# PSOC_10pin_to_ZIF.net
KiCad netlist of a schematic drawn in EAGLE
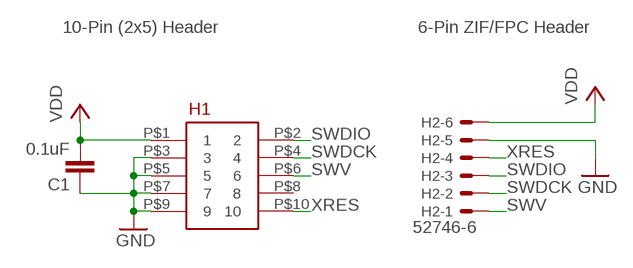
[diagram p0: schematic, sheet 1]

(export (version "E")
  (design (tool "Eeschema 10.0.6"))
  (components
    (comp (ref "C1")
      (value "0.1uF")
      (footprint "eagle-import:CAPC1608X90N")
      (libsource (lib "eagle-import") (part "CC0603-N"))
    )
    (comp (ref "H1")
      (value "2X5_SMD_HEADER_1.27MM")
      (footprint "eagle-import:2X5_SMD_HEADER_1.27MM")
      (libsource (lib "eagle-import") (part "2X5_SMD_HEADER_1.27MM"))
    )
    (comp (ref "H2")
      (value "52746-6")
      (footprint "eagle-import:52746-6")
      (libsource (lib "eagle-import") (part "52746-6"))
    )
  )
  (nets
    (net (code "1") (name "/SWDCK") (class "Default")
      (node (ref "H1") (pin "P$4") (pinfunction "4_P$4") (pintype "bidirectional"))
      (node (ref "H2") (pin "2") (pinfunction "S_2") (pintype "passive"))
    )
    (net (code "2") (name "/SWDIO") (class "Default")
      (node (ref "H1") (pin "P$2") (pinfunction "2_P$2") (pintype "bidirectional"))
      (node (ref "H2") (pin "3") (pinfunction "S_3") (pintype "passive"))
    )
    (net (code "3") (name "/SWV") (class "Default")
      (node (ref "H1") (pin "P$6") (pinfunction "6_P$6") (pintype "bidirectional"))
      (node (ref "H2") (pin "1") (pinfunction "S_1") (pintype "passive"))
    )
    (net (code "4") (name "/XRES") (class "Default")
      (node (ref "H1") (pin "P$10") (pinfunction "10_P$10") (pintype "bidirectional"))
      (node (ref "H2") (pin "4") (pinfunction "S_4") (pintype "passive"))
    )
    (net (code "5") (name "GND") (class "Default")
      (node (ref "C1") (pin "1") (pinfunction "1_1") (pintype "passive"))
      (node (ref "H1") (pin "P$3") (pinfunction "3_P$3") (pintype "bidirectional"))
      (node (ref "H1") (pin "P$5") (pinfunction "5_P$5") (pintype "bidirectional"))
      (node (ref "H1") (pin "P$7") (pinfunction "7_P$7") (pintype "bidirectional"))
      (node (ref "H1") (pin "P$9") (pinfunction "9_P$9") (pintype "bidirectional"))
      (node (ref "H2") (pin "5") (pinfunction "S_5") (pintype "passive"))
    )
    (net (code "6") (name "VDD") (class "Default")
      (node (ref "C1") (pin "2") (pinfunction "2_2") (pintype "passive"))
      (node (ref "H1") (pin "P$1") (pinfunction "1_P$1") (pintype "bidirectional"))
      (node (ref "H2") (pin "6") (pinfunction "S_6") (pintype "passive"))
    )
    (net (code "7") (name "unconnected-(H1-8-PadP$8)") (class "Default")
      (node (ref "H1") (pin "P$8") (pinfunction "8_P$8") (pintype "bidirectional"))
    )
  )
)
